# V4.net
KiCad netlist of a schematic drawn in Altium Designer
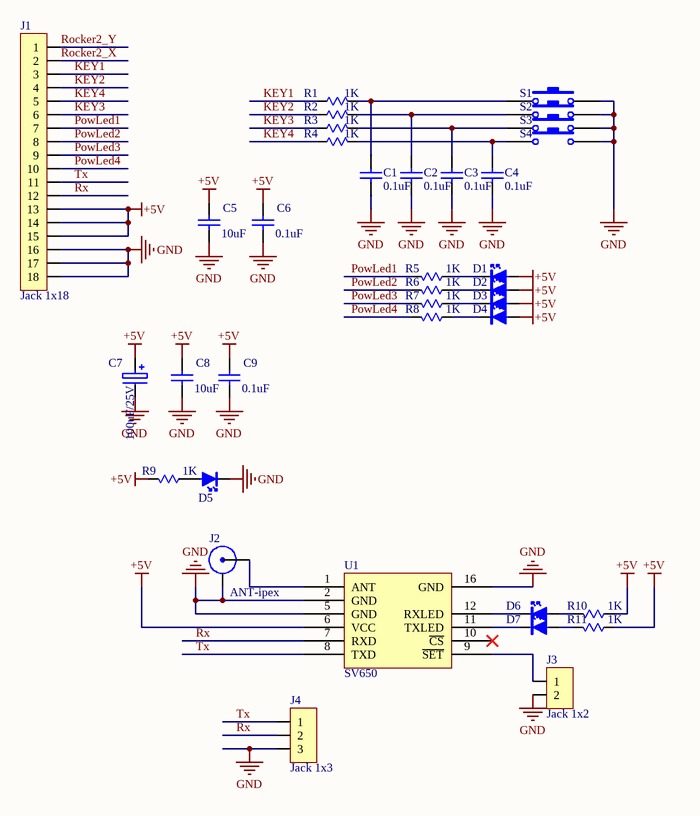
[diagram p0: 海关全向控制器数传转接板V4.SchDoc]

(export (version "E")
  (design (tool "Eeschema 10.0.6"))
  (components
    (comp (ref "C1") (value "0.1uF") (footprint "C0805") (libsource (lib "SMD") (part "Cap Semi")))
    (comp (ref "C2") (value "0.1uF") (footprint "C0805") (libsource (lib "SMD") (part "Cap Semi")))
    (comp (ref "C3") (value "0.1uF") (footprint "C0805") (libsource (lib "SMD") (part "Cap Semi")))
    (comp (ref "C4") (value "0.1uF") (footprint "C0805") (libsource (lib "SMD") (part "Cap Semi")))
    (comp (ref "C5") (value "10uF") (footprint "C0805") (libsource (lib "SMD") (part "Cap Semi")))
    (comp (ref "C6") (value "0.1uF") (footprint "C0805") (libsource (lib "SMD") (part "Cap Semi")))
    (comp (ref "C7") (value "100uF/25V") (footprint "C7343") (libsource (lib "RLCYDF") (part "Cap Poll")))
    (comp (ref "C8") (value "10uF") (footprint "C0805") (libsource (lib "SMD") (part "Cap Semi")))
    (comp (ref "C9") (value "0.1uF") (footprint "C0805") (libsource (lib "SMD") (part "Cap Semi")))
    (comp (ref "D1")
      (value "LED")
      (footprint "LED0805")
      (libsource (lib "Passive Components Class") (part "LED"))
    )
    (comp (ref "D2")
      (value "LED")
      (footprint "LED0805")
      (libsource (lib "Passive Components Class") (part "LED"))
    )
    (comp (ref "D3")
      (value "LED")
      (footprint "LED0805")
      (libsource (lib "Passive Components Class") (part "LED"))
    )
    (comp (ref "D4")
      (value "LED")
      (footprint "LED0805")
      (libsource (lib "Passive Components Class") (part "LED"))
    )
    (comp (ref "D5")
      (value "LED")
      (footprint "LED0805")
      (libsource (lib "Passive Components Class") (part "LED"))
    )
    (comp (ref "D6")
      (value "LED")
      (footprint "LED0805")
      (libsource (lib "Passive Components Class") (part "LED"))
    )
    (comp (ref "D7")
      (value "LED")
      (footprint "LED0805")
      (libsource (lib "Passive Components Class") (part "LED"))
    )
    (comp (ref "J1")
      (value "Jack 1x18")
      (footprint "0.5S-6X-18PB")
      (description "插座")
      (libsource (lib "Connector") (part "Jack 1x18"))
    )
    (comp (ref "J2") (value "ANT-ipex") (footprint "IPEX") (libsource (lib "RLCYDF") (part "ANT-ipex")))
    (comp (ref "J3")
      (value "Jack 1x2")
      (footprint "A6S-1101-PH")
      (description "插座")
      (libsource (lib "Connector") (part "Jack 1x2"))
    )
    (comp (ref "J4")
      (value "Jack 1x3")
      (footprint "Jk1*3-2.0")
      (description "插座")
      (libsource (lib "Connector") (part "Jack 1x3"))
    )
    (comp (ref "R1")
      (value "1K")
      (footprint "R0805")
      (description "Resistor")
      (fields (field (name "PUBLISHER") "Altium Limited"))
      (libsource (lib "UP-Robot") (part "Res"))
    )
    (comp (ref "R2")
      (value "1K")
      (footprint "R0805")
      (description "Resistor")
      (fields (field (name "PUBLISHER") "Altium Limited"))
      (libsource (lib "UP-Robot") (part "Res"))
    )
    (comp (ref "R3")
      (value "1K")
      (footprint "R0805")
      (description "Resistor")
      (fields (field (name "PUBLISHER") "Altium Limited"))
      (libsource (lib "UP-Robot") (part "Res"))
    )
    (comp (ref "R4")
      (value "1K")
      (footprint "R0805")
      (description "Resistor")
      (fields (field (name "PUBLISHER") "Altium Limited"))
      (libsource (lib "UP-Robot") (part "Res"))
    )
    (comp (ref "R5")
      (value "1K")
      (footprint "R0805")
      (description "Resistor")
      (fields (field (name "PUBLISHER") "Altium Limited"))
      (libsource (lib "UP-Robot") (part "Res"))
    )
    (comp (ref "R6")
      (value "1K")
      (footprint "R0805")
      (description "Resistor")
      (fields (field (name "PUBLISHER") "Altium Limited"))
      (libsource (lib "UP-Robot") (part "Res"))
    )
    (comp (ref "R7")
      (value "1K")
      (footprint "R0805")
      (description "Resistor")
      (fields (field (name "PUBLISHER") "Altium Limited"))
      (libsource (lib "UP-Robot") (part "Res"))
    )
    (comp (ref "R8")
      (value "1K")
      (footprint "R0805")
      (description "Resistor")
      (fields (field (name "PUBLISHER") "Altium Limited"))
      (libsource (lib "UP-Robot") (part "Res"))
    )
    (comp (ref "R9")
      (value "1K")
      (footprint "R0805")
      (description "Resistor")
      (fields (field (name "PUBLISHER") "Altium Limited"))
      (libsource (lib "UP-Robot") (part "Res"))
    )
    (comp (ref "R10")
      (value "1K")
      (footprint "R0805")
      (description "Resistor")
      (fields (field (name "PUBLISHER") "Altium Limited"))
      (libsource (lib "UP-Robot") (part "Res"))
    )
    (comp (ref "R11")
      (value "1K")
      (footprint "R0805")
      (description "Resistor")
      (fields (field (name "PUBLISHER") "Altium Limited"))
      (libsource (lib "UP-Robot") (part "Res"))
    )
    (comp (ref "S1")
      (value "SW-PB")
      (footprint "SW3X6X5")
      (description "Switch")
      (fields (field (name "PUBLISHER") "Altium Limited"))
      (libsource (lib "Miscellaneous Devices") (part "SW-PB"))
    )
    (comp (ref "S2")
      (value "SW-PB")
      (footprint "SW3X6X5")
      (description "Switch")
      (fields (field (name "PUBLISHER") "Altium Limited"))
      (libsource (lib "Miscellaneous Devices") (part "SW-PB"))
    )
    (comp (ref "S3")
      (value "SW-PB")
      (footprint "SW3X6X5")
      (description "Switch")
      (fields (field (name "PUBLISHER") "Altium Limited"))
      (libsource (lib "Miscellaneous Devices") (part "SW-PB"))
    )
    (comp (ref "S4")
      (value "SW-PB")
      (footprint "SW3X6X5")
      (description "Switch")
      (fields (field (name "PUBLISHER") "Altium Limited"))
      (libsource (lib "Miscellaneous Devices") (part "SW-PB"))
    )
    (comp (ref "U1") (value "SV650") (footprint "SV650") (libsource (lib "Module") (part "SV650")))
  )
  (nets
    (net (code "1") (name "+5V") (class "Default")
      (node (ref "C5") (pin "2") (pinfunction "2_2") (pintype "passive"))
      (node (ref "C6") (pin "2") (pinfunction "2_2") (pintype "passive"))
      (node (ref "C7") (pin "1") (pinfunction "1_1") (pintype "passive"))
      (node (ref "C8") (pin "2") (pinfunction "2_2") (pintype "passive"))
      (node (ref "C9") (pin "2") (pinfunction "2_2") (pintype "passive"))
      (node (ref "D1") (pin "1") (pinfunction "A_1") (pintype "passive"))
      (node (ref "D2") (pin "1") (pinfunction "A_1") (pintype "passive"))
      (node (ref "D3") (pin "1") (pinfunction "A_1") (pintype "passive"))
      (node (ref "D4") (pin "1") (pinfunction "A_1") (pintype "passive"))
      (node (ref "J1") (pin "13") (pinfunction "13_13") (pintype "passive"))
      (node (ref "J1") (pin "14") (pinfunction "14_14") (pintype "passive"))
      (node (ref "J1") (pin "15") (pinfunction "15_15") (pintype "passive"))
      (node (ref "R10") (pin "1") (pinfunction "1_1") (pintype "passive"))
      (node (ref "R11") (pin "1") (pinfunction "1_1") (pintype "passive"))
      (node (ref "R9") (pin "2") (pinfunction "2_2") (pintype "passive"))
      (node (ref "U1") (pin "6") (pinfunction "VCC_6") (pintype "passive"))
    )
    (net (code "2") (name "/KEY1") (class "Default")
      (node (ref "J1") (pin "3") (pinfunction "3_3") (pintype "passive"))
      (node (ref "R1") (pin "1") (pinfunction "1_1") (pintype "passive"))
    )
    (net (code "3") (name "/KEY2") (class "Default")
      (node (ref "J1") (pin "4") (pinfunction "4_4") (pintype "passive"))
      (node (ref "R2") (pin "1") (pinfunction "1_1") (pintype "passive"))
    )
    (net (code "4") (name "/KEY3") (class "Default")
      (node (ref "J1") (pin "6") (pinfunction "6_6") (pintype "passive"))
      (node (ref "R3") (pin "1") (pinfunction "1_1") (pintype "passive"))
    )
    (net (code "5") (name "/KEY4") (class "Default")
      (node (ref "J1") (pin "5") (pinfunction "5_5") (pintype "passive"))
      (node (ref "R4") (pin "1") (pinfunction "1_1") (pintype "passive"))
    )
    (net (code "6") (name "/PowLed1") (class "Default")
      (node (ref "J1") (pin "7") (pinfunction "7_7") (pintype "passive"))
      (node (ref "R5") (pin "2") (pinfunction "2_2") (pintype "passive"))
    )
    (net (code "7") (name "/PowLed2") (class "Default")
      (node (ref "J1") (pin "8") (pinfunction "8_8") (pintype "passive"))
      (node (ref "R6") (pin "2") (pinfunction "2_2") (pintype "passive"))
    )
    (net (code "8") (name "/PowLed3") (class "Default")
      (node (ref "J1") (pin "9") (pinfunction "9_9") (pintype "passive"))
      (node (ref "R7") (pin "2") (pinfunction "2_2") (pintype "passive"))
    )
    (net (code "9") (name "/PowLed4") (class "Default")
      (node (ref "J1") (pin "10") (pinfunction "10_10") (pintype "passive"))
      (node (ref "R8") (pin "2") (pinfunction "2_2") (pintype "passive"))
    )
    (net (code "10") (name "/Rocker2_X") (class "Default")
      (node (ref "J1") (pin "2") (pinfunction "2_2") (pintype "passive"))
    )
    (net (code "11") (name "/Rocker2_Y") (class "Default")
      (node (ref "J1") (pin "1") (pinfunction "1_1") (pintype "passive"))
    )
    (net (code "12") (name "/Rx") (class "Default")
      (node (ref "J1") (pin "12") (pinfunction "12_12") (pintype "passive"))
      (node (ref "J4") (pin "2") (pinfunction "2_2") (pintype "passive"))
      (node (ref "U1") (pin "7") (pinfunction "RXD_7") (pintype "passive"))
    )
    (net (code "13") (name "/Tx") (class "Default")
      (node (ref "J1") (pin "11") (pinfunction "11_11") (pintype "passive"))
      (node (ref "J4") (pin "1") (pinfunction "1_1") (pintype "passive"))
      (node (ref "U1") (pin "8") (pinfunction "TXD_8") (pintype "passive"))
    )
    (net (code "14") (name "GND") (class "Default")
      (node (ref "C1") (pin "1") (pinfunction "1_1") (pintype "passive"))
      (node (ref "C2") (pin "1") (pinfunction "1_1") (pintype "passive"))
      (node (ref "C3") (pin "1") (pinfunction "1_1") (pintype "passive"))
      (node (ref "C4") (pin "1") (pinfunction "1_1") (pintype "passive"))
      (node (ref "C5") (pin "1") (pinfunction "1_1") (pintype "passive"))
      (node (ref "C6") (pin "1") (pinfunction "1_1") (pintype "passive"))
      (node (ref "C7") (pin "2") (pinfunction "2_2") (pintype "passive"))
      (node (ref "C8") (pin "1") (pinfunction "1_1") (pintype "passive"))
      (node (ref "C9") (pin "1") (pinfunction "1_1") (pintype "passive"))
      (node (ref "D5") (pin "2") (pinfunction "K_2") (pintype "passive"))
      (node (ref "J1") (pin "16") (pinfunction "16_16") (pintype "passive"))
      (node (ref "J1") (pin "17") (pinfunction "17_17") (pintype "passive"))
      (node (ref "J1") (pin "18") (pinfunction "18_18") (pintype "passive"))
      (node (ref "J2") (pin "2") (pinfunction "GND_2") (pintype "passive"))
      (node (ref "J3") (pin "2") (pinfunction "2_2") (pintype "passive"))
      (node (ref "J4") (pin "3") (pinfunction "3_3") (pintype "passive"))
      (node (ref "S1") (pin "2") (pinfunction "2_2") (pintype "passive"))
      (node (ref "S2") (pin "2") (pinfunction "2_2") (pintype "passive"))
      (node (ref "S3") (pin "2") (pinfunction "2_2") (pintype "passive"))
      (node (ref "S4") (pin "2") (pinfunction "2_2") (pintype "passive"))
      (node (ref "U1") (pin "16") (pinfunction "GND_16") (pintype "passive"))
      (node (ref "U1") (pin "2") (pinfunction "GND_2") (pintype "passive"))
      (node (ref "U1") (pin "5") (pinfunction "GND_5") (pintype "passive"))
    )
    (net (code "15") (name "Net-(C1-Pad2)") (class "Default")
      (node (ref "C1") (pin "2") (pinfunction "2_2") (pintype "passive"))
      (node (ref "R1") (pin "2") (pinfunction "2_2") (pintype "passive"))
      (node (ref "S1") (pin "1") (pinfunction "1_1") (pintype "passive"))
    )
    (net (code "16") (name "Net-(C2-Pad2)") (class "Default")
      (node (ref "C2") (pin "2") (pinfunction "2_2") (pintype "passive"))
      (node (ref "R2") (pin "2") (pinfunction "2_2") (pintype "passive"))
      (node (ref "S2") (pin "1") (pinfunction "1_1") (pintype "passive"))
    )
    (net (code "17") (name "Net-(C3-Pad2)") (class "Default")
      (node (ref "C3") (pin "2") (pinfunction "2_2") (pintype "passive"))
      (node (ref "R3") (pin "2") (pinfunction "2_2") (pintype "passive"))
      (node (ref "S3") (pin "1") (pinfunction "1_1") (pintype "passive"))
    )
    (net (code "18") (name "Net-(C4-Pad2)") (class "Default")
      (node (ref "C4") (pin "2") (pinfunction "2_2") (pintype "passive"))
      (node (ref "R4") (pin "2") (pinfunction "2_2") (pintype "passive"))
      (node (ref "S4") (pin "1") (pinfunction "1_1") (pintype "passive"))
    )
    (net (code "19") (name "Net-(D1-K)") (class "Default")
      (node (ref "D1") (pin "2") (pinfunction "K_2") (pintype "passive"))
      (node (ref "R5") (pin "1") (pinfunction "1_1") (pintype "passive"))
    )
    (net (code "20") (name "Net-(D2-K)") (class "Default")
      (node (ref "D2") (pin "2") (pinfunction "K_2") (pintype "passive"))
      (node (ref "R6") (pin "1") (pinfunction "1_1") (pintype "passive"))
    )
    (net (code "21") (name "Net-(D3-K)") (class "Default")
      (node (ref "D3") (pin "2") (pinfunction "K_2") (pintype "passive"))
      (node (ref "R7") (pin "1") (pinfunction "1_1") (pintype "passive"))
    )
    (net (code "22") (name "Net-(D4-K)") (class "Default")
      (node (ref "D4") (pin "2") (pinfunction "K_2") (pintype "passive"))
      (node (ref "R8") (pin "1") (pinfunction "1_1") (pintype "passive"))
    )
    (net (code "23") (name "Net-(D5-A)") (class "Default")
      (node (ref "D5") (pin "1") (pinfunction "A_1") (pintype "passive"))
      (node (ref "R9") (pin "1") (pinfunction "1_1") (pintype "passive"))
    )
    (net (code "24") (name "Net-(D6-A)") (class "Default")
      (node (ref "D6") (pin "1") (pinfunction "A_1") (pintype "passive"))
      (node (ref "R10") (pin "2") (pinfunction "2_2") (pintype "passive"))
    )
    (net (code "25") (name "Net-(D6-K)") (class "Default")
      (node (ref "D6") (pin "2") (pinfunction "K_2") (pintype "passive"))
      (node (ref "U1") (pin "12") (pinfunction "RXLED_12") (pintype "passive"))
    )
    (net (code "26") (name "Net-(D7-A)") (class "Default")
      (node (ref "D7") (pin "1") (pinfunction "A_1") (pintype "passive"))
      (node (ref "R11") (pin "2") (pinfunction "2_2") (pintype "passive"))
    )
    (net (code "27") (name "Net-(D7-K)") (class "Default")
      (node (ref "D7") (pin "2") (pinfunction "K_2") (pintype "passive"))
      (node (ref "U1") (pin "11") (pinfunction "TXLED_11") (pintype "passive"))
    )
    (net (code "28") (name "Net-(J2-ANT)") (class "Default")
      (node (ref "J2") (pin "1") (pinfunction "ANT_1") (pintype "passive"))
      (node (ref "U1") (pin "1") (pinfunction "ANT_1") (pintype "passive"))
    )
    (net (code "29") (name "Net-(U1-~{SET})") (class "Default")
      (node (ref "J3") (pin "1") (pinfunction "1_1") (pintype "passive"))
      (node (ref "U1") (pin "9") (pinfunction "~{SET}_9") (pintype "passive"))
    )
    (net (code "30") (name "unconnected-(U1-~{CS}-Pad10)") (class "Default")
      (node (ref "U1") (pin "10") (pinfunction "~{CS}_10") (pintype "passive+no_connect"))
    )
  )
)
